# Bananna_board.net
KiCad netlist of a schematic drawn in EAGLE
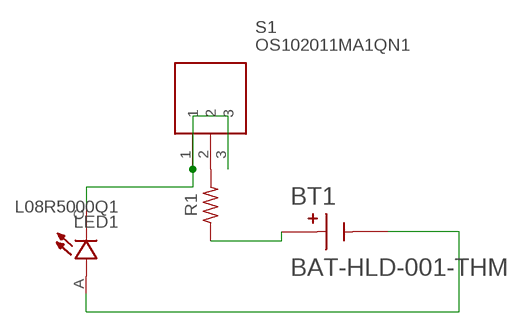
[diagram p0: schematic, sheet 1]

(export (version "E")
  (design (tool "Eeschema 10.0.6"))
  (components
    (comp (ref "BT1")
      (value "BAT-HLD-001-THM")
      (footprint "eagle-import:BAT_BAT-HLD-001-THM")
      (fields (field (name "DIGI-KEY_PART_NUMBER") "BAT-HLD-001-THM-ND") (field (name "MF") "Linx"))
      (libsource (lib "eagle-import") (part "BAT-HLD-001-THM"))
    )
    (comp (ref "LED1")
      (value "L08R5000Q1")
      (footprint "eagle-import:LEDRD254W57D500H1070")
      (fields (field (name "MF") "LED Technology"))
      (libsource (lib "eagle-import") (part "L08R5000Q1"))
    )
    (comp (ref "R1")
      (value "R-US_0207/12")
      (footprint "eagle-import:0207_12")
      (libsource (lib "eagle-import") (part "R-US_0207/12"))
    )
    (comp (ref "S1")
      (value "OS102011MA1QN1")
      (footprint "eagle-import:OS102011MA1QN1")
      (fields (field (name "MOUSER_PART_NUMBER") "611-OS102011MA1QN1"))
      (libsource (lib "eagle-import") (part "OS102011MA1QN1"))
    )
  )
  (nets
    (net (code "1") (name "Net-(BT1-P-PadP1)") (class "Default")
      (node (ref "BT1") (pin "P1") (pinfunction "P_P1") (pintype "passive"))
      (node (ref "BT1") (pin "P2") (pinfunction "P_P2") (pintype "passive"))
      (node (ref "BT1") (pin "P3") (pinfunction "P_P3") (pintype "passive"))
      (node (ref "BT1") (pin "P4") (pinfunction "P_P4") (pintype "passive"))
      (node (ref "R1") (pin "1") (pinfunction "1_1") (pintype "passive"))
    )
    (net (code "2") (name "Net-(BT1-PadN)") (class "Default")
      (node (ref "BT1") (pin "N") (pinfunction "N_N") (pintype "passive"))
      (node (ref "LED1") (pin "A") (pinfunction "A_A") (pintype "passive"))
    )
    (net (code "3") (name "Net-(LED1-PadC)") (class "Default")
      (node (ref "LED1") (pin "C") (pinfunction "C_C") (pintype "passive"))
      (node (ref "S1") (pin "1") (pinfunction "1_1") (pintype "bidirectional"))
      (node (ref "S1") (pin "3") (pinfunction "3_3") (pintype "bidirectional"))
    )
    (net (code "4") (name "Net-(R1-Pad2)") (class "Default")
      (node (ref "R1") (pin "2") (pinfunction "2_2") (pintype "passive"))
      (node (ref "S1") (pin "2") (pinfunction "2_2") (pintype "bidirectional"))
    )
  )
)
